# Tic_Tac_Toe.net
KiCad netlist of a schematic drawn in EAGLE
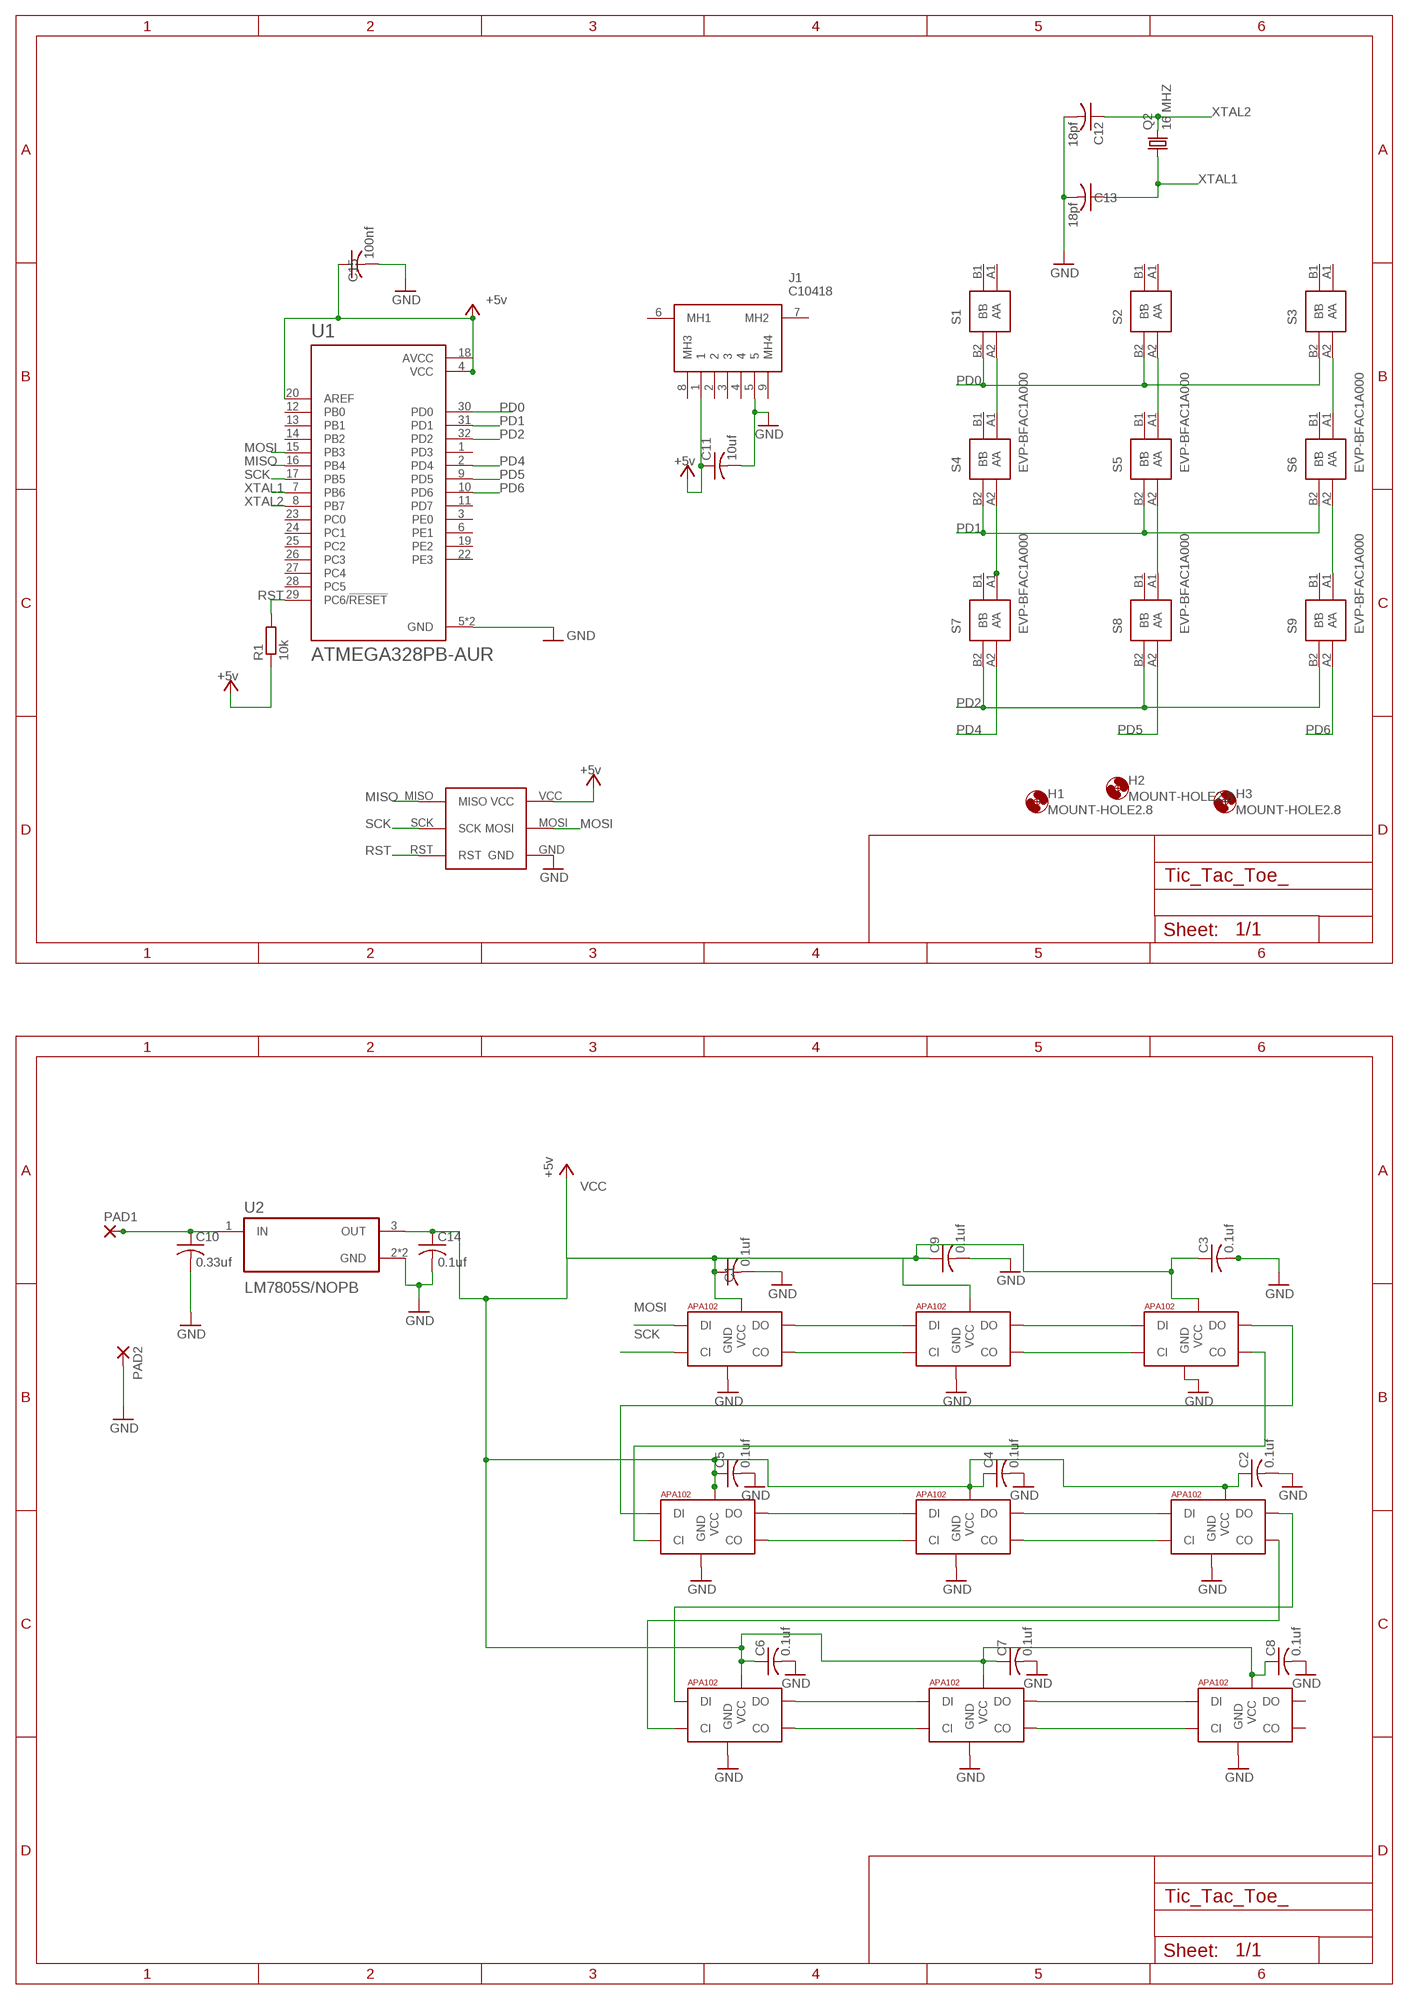
[diagram p0: schematic, sheet 1]

(export (version "E")
  (design (tool "Eeschema 10.0.6"))
  (components
    (comp (ref "C1")
      (value "0.1uf")
      (footprint "eagle-import:C0805")
      (libsource (lib "eagle-import") (part "C-USC0805"))
    )
    (comp (ref "C2")
      (value "0.1uf")
      (footprint "eagle-import:C0805")
      (libsource (lib "eagle-import") (part "C-USC0805"))
    )
    (comp (ref "C3")
      (value "0.1uf")
      (footprint "eagle-import:C0805")
      (libsource (lib "eagle-import") (part "C-USC0805"))
    )
    (comp (ref "C4")
      (value "0.1uf")
      (footprint "eagle-import:C0805")
      (libsource (lib "eagle-import") (part "C-USC0805"))
    )
    (comp (ref "C5")
      (value "0.1uf")
      (footprint "eagle-import:C0805")
      (libsource (lib "eagle-import") (part "C-USC0805"))
    )
    (comp (ref "C6")
      (value "0.1uf")
      (footprint "eagle-import:C0805")
      (libsource (lib "eagle-import") (part "C-USC0805"))
    )
    (comp (ref "C7")
      (value "0.1uf")
      (footprint "eagle-import:C0805")
      (libsource (lib "eagle-import") (part "C-USC0805"))
    )
    (comp (ref "C8")
      (value "0.1uf")
      (footprint "eagle-import:C0805")
      (libsource (lib "eagle-import") (part "C-USC0805"))
    )
    (comp (ref "C9")
      (value "0.1uf")
      (footprint "eagle-import:C0805")
      (libsource (lib "eagle-import") (part "C-USC0805"))
    )
    (comp (ref "C10")
      (value "0.33uf")
      (footprint "eagle-import:C0805")
      (libsource (lib "eagle-import") (part "C-USC0805"))
    )
    (comp (ref "C11")
      (value "10uf")
      (footprint "eagle-import:C0805")
      (libsource (lib "eagle-import") (part "C-USC0805"))
    )
    (comp (ref "C12")
      (value "18pf")
      (footprint "eagle-import:C0805")
      (libsource (lib "eagle-import") (part "C-USC0805"))
    )
    (comp (ref "C13")
      (value "18pf")
      (footprint "eagle-import:C0805")
      (libsource (lib "eagle-import") (part "C-USC0805"))
    )
    (comp (ref "C14")
      (value "0.1uf")
      (footprint "eagle-import:C0805")
      (libsource (lib "eagle-import") (part "C-USC0805"))
    )
    (comp (ref "C15")
      (value "100nf")
      (footprint "eagle-import:C0805")
      (libsource (lib "eagle-import") (part "C-USC0805"))
    )
    (comp (ref "H1")
      (value "MOUNT-HOLE2.8")
      (footprint "eagle-import:2,8")
      (libsource (lib "eagle-import") (part "MOUNT-HOLE2.8"))
    )
    (comp (ref "H2")
      (value "MOUNT-HOLE2.8")
      (footprint "eagle-import:2,8")
      (libsource (lib "eagle-import") (part "MOUNT-HOLE2.8"))
    )
    (comp (ref "H3")
      (value "MOUNT-HOLE2.8")
      (footprint "eagle-import:2,8")
      (libsource (lib "eagle-import") (part "MOUNT-HOLE2.8"))
    )
    (comp (ref "J1")
      (value "C10418")
      (footprint "eagle-import:C10418")
      (libsource (lib "eagle-import") (part "C10418"))
    )
    (comp (ref "PAD1")
      (value "2,15/1,0")
      (footprint "eagle-import:2,15_1,0")
      (libsource (lib "eagle-import") (part "2,15/1,0"))
    )
    (comp (ref "PAD2")
      (value "2,15/1,0")
      (footprint "eagle-import:2,15_1,0")
      (libsource (lib "eagle-import") (part "2,15/1,0"))
    )
    (comp (ref "Q2")
      (value "16 MHZ")
      (footprint "eagle-import:HC49UP")
      (libsource (lib "eagle-import") (part "CRYSTALHC49UP"))
    )
    (comp (ref "R1")
      (value "10k")
      (footprint "eagle-import:M0805")
      (libsource (lib "eagle-import") (part "R-EU_M0805"))
    )
    (comp (ref "S1")
      (value "EVP-BFAC1A000")
      (footprint "eagle-import:EVPBFAC1A000")
      (fields (field (name "MF") "Panasonic Electronic"))
      (libsource (lib "eagle-import") (part "EVP-BFAC1A000"))
    )
    (comp (ref "S2")
      (value "EVP-BFAC1A000")
      (footprint "eagle-import:EVPBFAC1A000")
      (fields (field (name "MF") "Panasonic Electronic"))
      (libsource (lib "eagle-import") (part "EVP-BFAC1A000"))
    )
    (comp (ref "S3")
      (value "EVP-BFAC1A000")
      (footprint "eagle-import:EVPBFAC1A000")
      (fields (field (name "MF") "Panasonic Electronic"))
      (libsource (lib "eagle-import") (part "EVP-BFAC1A000"))
    )
    (comp (ref "S4")
      (value "EVP-BFAC1A000")
      (footprint "eagle-import:EVPBFAC1A000")
      (fields (field (name "MF") "Panasonic Electronic"))
      (libsource (lib "eagle-import") (part "EVP-BFAC1A000"))
    )
    (comp (ref "S5")
      (value "EVP-BFAC1A000")
      (footprint "eagle-import:EVPBFAC1A000")
      (fields (field (name "MF") "Panasonic Electronic"))
      (libsource (lib "eagle-import") (part "EVP-BFAC1A000"))
    )
    (comp (ref "S6")
      (value "EVP-BFAC1A000")
      (footprint "eagle-import:EVPBFAC1A000")
      (fields (field (name "MF") "Panasonic Electronic"))
      (libsource (lib "eagle-import") (part "EVP-BFAC1A000"))
    )
    (comp (ref "S7")
      (value "EVP-BFAC1A000")
      (footprint "eagle-import:EVPBFAC1A000")
      (fields (field (name "MF") "Panasonic Electronic"))
      (libsource (lib "eagle-import") (part "EVP-BFAC1A000"))
    )
    (comp (ref "S8")
      (value "EVP-BFAC1A000")
      (footprint "eagle-import:EVPBFAC1A000")
      (fields (field (name "MF") "Panasonic Electronic"))
      (libsource (lib "eagle-import") (part "EVP-BFAC1A000"))
    )
    (comp (ref "S9")
      (value "EVP-BFAC1A000")
      (footprint "eagle-import:EVPBFAC1A000")
      (fields (field (name "MF") "Panasonic Electronic"))
      (libsource (lib "eagle-import") (part "EVP-BFAC1A000"))
    )
    (comp (ref "U$1")
      (value "AVR-ISP")
      (footprint "eagle-import:AVR-ISP")
      (fields (field (name "MF") "Gravitech"))
      (libsource (lib "eagle-import") (part "AVR-ISP"))
    )
    (comp (ref "U$2")
      (value "APA1025050")
      (footprint "eagle-import:APA102_5050")
      (libsource (lib "eagle-import") (part "APA1025050"))
    )
    (comp (ref "U$3")
      (value "APA1025050")
      (footprint "eagle-import:APA102_5050")
      (libsource (lib "eagle-import") (part "APA1025050"))
    )
    (comp (ref "U$4")
      (value "APA1025050")
      (footprint "eagle-import:APA102_5050")
      (libsource (lib "eagle-import") (part "APA1025050"))
    )
    (comp (ref "U$5")
      (value "APA1025050")
      (footprint "eagle-import:APA102_5050")
      (libsource (lib "eagle-import") (part "APA1025050"))
    )
    (comp (ref "U$6")
      (value "APA1025050")
      (footprint "eagle-import:APA102_5050")
      (libsource (lib "eagle-import") (part "APA1025050"))
    )
    (comp (ref "U$7")
      (value "APA1025050")
      (footprint "eagle-import:APA102_5050")
      (libsource (lib "eagle-import") (part "APA1025050"))
    )
    (comp (ref "U$8")
      (value "APA1025050")
      (footprint "eagle-import:APA102_5050")
      (libsource (lib "eagle-import") (part "APA1025050"))
    )
    (comp (ref "U$9")
      (value "APA1025050")
      (footprint "eagle-import:APA102_5050")
      (libsource (lib "eagle-import") (part "APA1025050"))
    )
    (comp (ref "U$10")
      (value "APA1025050")
      (footprint "eagle-import:APA102_5050")
      (libsource (lib "eagle-import") (part "APA1025050"))
    )
    (comp (ref "U1")
      (value "ATMEGA328PB-AUR")
      (footprint "eagle-import:QFP80P900X900X120-32N")
      (fields (field (name "DIGI-KEY_PART_NUMBER") "ATMEGA328PB-AURCT-ND") (field (name "MF") "Microchip"))
      (libsource (lib "eagle-import") (part "ATMEGA328PB-AUR"))
    )
    (comp (ref "U2")
      (value "LM7805S/NOPB")
      (footprint "eagle-import:TO254P1524X483-4N")
      (fields (field (name "MF") "Texas Instruments"))
      (libsource (lib "eagle-import") (part "LM7805S/NOPB"))
    )
  )
  (nets
    (net (code "1") (name "+5v") (class "Default")
      (node (ref "C1") (pin "1") (pinfunction "1_1") (pintype "passive"))
      (node (ref "C11") (pin "1") (pinfunction "1_1") (pintype "passive"))
      (node (ref "C14") (pin "1") (pinfunction "1_1") (pintype "passive"))
      (node (ref "C15") (pin "1") (pinfunction "1_1") (pintype "passive"))
      (node (ref "C2") (pin "1") (pinfunction "1_1") (pintype "passive"))
      (node (ref "C3") (pin "1") (pinfunction "1_1") (pintype "passive"))
      (node (ref "C4") (pin "1") (pinfunction "1_1") (pintype "passive"))
      (node (ref "C5") (pin "1") (pinfunction "1_1") (pintype "passive"))
      (node (ref "C6") (pin "1") (pinfunction "1_1") (pintype "passive"))
      (node (ref "C7") (pin "1") (pinfunction "1_1") (pintype "passive"))
      (node (ref "C8") (pin "1") (pinfunction "1_1") (pintype "passive"))
      (node (ref "C9") (pin "1") (pinfunction "1_1") (pintype "passive"))
      (node (ref "J1") (pin "1") (pinfunction "1_1") (pintype "bidirectional"))
      (node (ref "R1") (pin "1") (pinfunction "1_1") (pintype "passive"))
      (node (ref "U$1") (pin "VCC") (pinfunction "VCC_VCC") (pintype "bidirectional"))
      (node (ref "U$10") (pin "1") (pinfunction "VCC_1") (pintype "bidirectional"))
      (node (ref "U$2") (pin "1") (pinfunction "VCC_1") (pintype "bidirectional"))
      (node (ref "U$3") (pin "1") (pinfunction "VCC_1") (pintype "bidirectional"))
      (node (ref "U$4") (pin "1") (pinfunction "VCC_1") (pintype "bidirectional"))
      (node (ref "U$5") (pin "1") (pinfunction "VCC_1") (pintype "bidirectional"))
      (node (ref "U$6") (pin "1") (pinfunction "VCC_1") (pintype "bidirectional"))
      (node (ref "U$7") (pin "1") (pinfunction "VCC_1") (pintype "bidirectional"))
      (node (ref "U$8") (pin "1") (pinfunction "VCC_1") (pintype "bidirectional"))
      (node (ref "U$9") (pin "1") (pinfunction "VCC_1") (pintype "bidirectional"))
      (node (ref "U1") (pin "18") (pinfunction "AVCC_18") (pintype "power_in"))
      (node (ref "U1") (pin "20") (pinfunction "AREF_20") (pintype "input"))
      (node (ref "U1") (pin "4") (pinfunction "VCC_4") (pintype "power_in"))
      (node (ref "U2") (pin "3") (pinfunction "OUT_3") (pintype "output"))
    )
    (net (code "2") (name "/MISO") (class "Default")
      (node (ref "U$1") (pin "MISO") (pinfunction "MISO_MISO") (pintype "bidirectional"))
      (node (ref "U1") (pin "16") (pinfunction "PB4_16") (pintype "bidirectional"))
    )
    (net (code "3") (name "/MOSI") (class "Default")
      (node (ref "U$1") (pin "MOSI") (pinfunction "MOSI_MOSI") (pintype "bidirectional"))
      (node (ref "U$2") (pin "4") (pinfunction "DI_4") (pintype "bidirectional"))
      (node (ref "U1") (pin "15") (pinfunction "PB3_15") (pintype "bidirectional"))
    )
    (net (code "4") (name "/PD0") (class "Default")
      (node (ref "S1") (pin "B2") (pinfunction "B'_B2") (pintype "bidirectional"))
      (node (ref "S2") (pin "B2") (pinfunction "B'_B2") (pintype "bidirectional"))
      (node (ref "S3") (pin "B2") (pinfunction "B'_B2") (pintype "bidirectional"))
      (node (ref "U1") (pin "30") (pinfunction "PD0_30") (pintype "bidirectional"))
    )
    (net (code "5") (name "/PD1") (class "Default")
      (node (ref "S4") (pin "B2") (pinfunction "B'_B2") (pintype "bidirectional"))
      (node (ref "S5") (pin "B2") (pinfunction "B'_B2") (pintype "bidirectional"))
      (node (ref "S6") (pin "B2") (pinfunction "B'_B2") (pintype "bidirectional"))
      (node (ref "U1") (pin "31") (pinfunction "PD1_31") (pintype "bidirectional"))
    )
    (net (code "6") (name "/PD2") (class "Default")
      (node (ref "S7") (pin "B2") (pinfunction "B'_B2") (pintype "bidirectional"))
      (node (ref "S8") (pin "B2") (pinfunction "B'_B2") (pintype "bidirectional"))
      (node (ref "S9") (pin "B2") (pinfunction "B'_B2") (pintype "bidirectional"))
      (node (ref "U1") (pin "32") (pinfunction "PD2_32") (pintype "bidirectional"))
    )
    (net (code "7") (name "/PD4") (class "Default")
      (node (ref "S7") (pin "A2") (pinfunction "A'_A2") (pintype "bidirectional"))
      (node (ref "U1") (pin "2") (pinfunction "PD4_2") (pintype "bidirectional"))
    )
    (net (code "8") (name "/PD5") (class "Default")
      (node (ref "S8") (pin "A2") (pinfunction "A'_A2") (pintype "bidirectional"))
      (node (ref "U1") (pin "9") (pinfunction "PD5_9") (pintype "bidirectional"))
    )
    (net (code "9") (name "/PD6") (class "Default")
      (node (ref "S9") (pin "A2") (pinfunction "A'_A2") (pintype "bidirectional"))
      (node (ref "U1") (pin "10") (pinfunction "PD6_10") (pintype "bidirectional"))
    )
    (net (code "10") (name "/RST") (class "Default")
      (node (ref "R1") (pin "2") (pinfunction "2_2") (pintype "passive"))
      (node (ref "U$1") (pin "RST") (pinfunction "RST_RST") (pintype "bidirectional"))
      (node (ref "U1") (pin "29") (pinfunction "PC6/~{RESET}_29") (pintype "bidirectional"))
    )
    (net (code "11") (name "/SCK") (class "Default")
      (node (ref "U$1") (pin "SCK") (pinfunction "SCK_SCK") (pintype "bidirectional"))
      (node (ref "U$2") (pin "5") (pinfunction "CI_5") (pintype "bidirectional"))
      (node (ref "U1") (pin "17") (pinfunction "PB5_17") (pintype "bidirectional"))
    )
    (net (code "12") (name "/XTAL1") (class "Default")
      (node (ref "C13") (pin "1") (pinfunction "1_1") (pintype "passive"))
      (node (ref "Q2") (pin "1") (pinfunction "1_1") (pintype "passive"))
      (node (ref "U1") (pin "7") (pinfunction "PB6_7") (pintype "bidirectional"))
    )
    (net (code "13") (name "/XTAL2") (class "Default")
      (node (ref "C12") (pin "1") (pinfunction "1_1") (pintype "passive"))
      (node (ref "Q2") (pin "2") (pinfunction "2_2") (pintype "passive"))
      (node (ref "U1") (pin "8") (pinfunction "PB7_8") (pintype "bidirectional"))
    )
    (net (code "14") (name "GND") (class "Default")
      (node (ref "C1") (pin "2") (pinfunction "2_2") (pintype "passive"))
      (node (ref "C10") (pin "2") (pinfunction "2_2") (pintype "passive"))
      (node (ref "C11") (pin "2") (pinfunction "2_2") (pintype "passive"))
      (node (ref "C12") (pin "2") (pinfunction "2_2") (pintype "passive"))
      (node (ref "C13") (pin "2") (pinfunction "2_2") (pintype "passive"))
      (node (ref "C14") (pin "2") (pinfunction "2_2") (pintype "passive"))
      (node (ref "C15") (pin "2") (pinfunction "2_2") (pintype "passive"))
      (node (ref "C2") (pin "2") (pinfunction "2_2") (pintype "passive"))
      (node (ref "C3") (pin "2") (pinfunction "2_2") (pintype "passive"))
      (node (ref "C4") (pin "2") (pinfunction "2_2") (pintype "passive"))
      (node (ref "C5") (pin "2") (pinfunction "2_2") (pintype "passive"))
      (node (ref "C6") (pin "2") (pinfunction "2_2") (pintype "passive"))
      (node (ref "C7") (pin "2") (pinfunction "2_2") (pintype "passive"))
      (node (ref "C8") (pin "2") (pinfunction "2_2") (pintype "passive"))
      (node (ref "C9") (pin "2") (pinfunction "2_2") (pintype "passive"))
      (node (ref "J1") (pin "5") (pinfunction "5_5") (pintype "bidirectional"))
      (node (ref "PAD2") (pin "1") (pinfunction "P_1") (pintype "passive"))
      (node (ref "U$1") (pin "GND") (pinfunction "GND_GND") (pintype "bidirectional"))
      (node (ref "U$10") (pin "6") (pinfunction "GND_6") (pintype "bidirectional"))
      (node (ref "U$2") (pin "6") (pinfunction "GND_6") (pintype "bidirectional"))
      (node (ref "U$3") (pin "6") (pinfunction "GND_6") (pintype "bidirectional"))
      (node (ref "U$4") (pin "6") (pinfunction "GND_6") (pintype "bidirectional"))
      (node (ref "U$5") (pin "6") (pinfunction "GND_6") (pintype "bidirectional"))
      (node (ref "U$6") (pin "6") (pinfunction "GND_6") (pintype "bidirectional"))
      (node (ref "U$7") (pin "6") (pinfunction "GND_6") (pintype "bidirectional"))
      (node (ref "U$8") (pin "6") (pinfunction "GND_6") (pintype "bidirectional"))
      (node (ref "U$9") (pin "6") (pinfunction "GND_6") (pintype "bidirectional"))
      (node (ref "U1") (pin "21") (pinfunction "GND_21") (pintype "power_in"))
      (node (ref "U1") (pin "5") (pinfunction "GND_5") (pintype "power_in"))
      (node (ref "U2") (pin "2") (pinfunction "GND_2") (pintype "power_in"))
      (node (ref "U2") (pin "4") (pinfunction "GND_4") (pintype "power_in"))
    )
    (net (code "15") (name "Net-(PAD1-P)") (class "Default")
      (node (ref "C10") (pin "1") (pinfunction "1_1") (pintype "passive"))
      (node (ref "PAD1") (pin "1") (pinfunction "P_1") (pintype "passive"))
      (node (ref "U2") (pin "1") (pinfunction "IN_1") (pintype "input"))
    )
    (net (code "16") (name "Net-(S1-A')") (class "Default")
      (node (ref "S1") (pin "A2") (pinfunction "A'_A2") (pintype "bidirectional"))
      (node (ref "S4") (pin "A1") (pinfunction "A_A1") (pintype "bidirectional"))
    )
    (net (code "17") (name "Net-(S2-A')") (class "Default")
      (node (ref "S2") (pin "A2") (pinfunction "A'_A2") (pintype "bidirectional"))
      (node (ref "S5") (pin "A1") (pinfunction "A_A1") (pintype "bidirectional"))
    )
    (net (code "18") (name "Net-(S3-A')") (class "Default")
      (node (ref "S3") (pin "A2") (pinfunction "A'_A2") (pintype "bidirectional"))
      (node (ref "S6") (pin "A1") (pinfunction "A_A1") (pintype "bidirectional"))
    )
    (net (code "19") (name "Net-(S4-A')") (class "Default")
      (node (ref "S4") (pin "A2") (pinfunction "A'_A2") (pintype "bidirectional"))
      (node (ref "S7") (pin "A1") (pinfunction "A_A1") (pintype "bidirectional"))
    )
    (net (code "20") (name "Net-(S5-A')") (class "Default")
      (node (ref "S5") (pin "A2") (pinfunction "A'_A2") (pintype "bidirectional"))
      (node (ref "S8") (pin "A1") (pinfunction "A_A1") (pintype "bidirectional"))
    )
    (net (code "21") (name "Net-(S6-A')") (class "Default")
      (node (ref "S6") (pin "A2") (pinfunction "A'_A2") (pintype "bidirectional"))
      (node (ref "S9") (pin "A1") (pinfunction "A_A1") (pintype "bidirectional"))
    )
    (net (code "22") (name "Net-(U$2-CO)") (class "Default")
      (node (ref "U$2") (pin "2") (pinfunction "CO_2") (pintype "bidirectional"))
      (node (ref "U$3") (pin "5") (pinfunction "CI_5") (pintype "bidirectional"))
    )
    (net (code "23") (name "Net-(U$2-DO)") (class "Default")
      (node (ref "U$2") (pin "3") (pinfunction "DO_3") (pintype "bidirectional"))
      (node (ref "U$3") (pin "4") (pinfunction "DI_4") (pintype "bidirectional"))
    )
    (net (code "24") (name "Net-(U$3-CO)") (class "Default")
      (node (ref "U$3") (pin "2") (pinfunction "CO_2") (pintype "bidirectional"))
      (node (ref "U$4") (pin "5") (pinfunction "CI_5") (pintype "bidirectional"))
    )
    (net (code "25") (name "Net-(U$3-DO)") (class "Default")
      (node (ref "U$3") (pin "3") (pinfunction "DO_3") (pintype "bidirectional"))
      (node (ref "U$4") (pin "4") (pinfunction "DI_4") (pintype "bidirectional"))
    )
    (net (code "26") (name "Net-(U$4-CO)") (class "Default")
      (node (ref "U$4") (pin "2") (pinfunction "CO_2") (pintype "bidirectional"))
      (node (ref "U$5") (pin "5") (pinfunction "CI_5") (pintype "bidirectional"))
    )
    (net (code "27") (name "Net-(U$4-DO)") (class "Default")
      (node (ref "U$4") (pin "3") (pinfunction "DO_3") (pintype "bidirectional"))
      (node (ref "U$5") (pin "4") (pinfunction "DI_4") (pintype "bidirectional"))
    )
    (net (code "28") (name "Net-(U$5-CO)") (class "Default")
      (node (ref "U$5") (pin "2") (pinfunction "CO_2") (pintype "bidirectional"))
      (node (ref "U$6") (pin "5") (pinfunction "CI_5") (pintype "bidirectional"))
    )
    (net (code "29") (name "Net-(U$5-DO)") (class "Default")
      (node (ref "U$5") (pin "3") (pinfunction "DO_3") (pintype "bidirectional"))
      (node (ref "U$6") (pin "4") (pinfunction "DI_4") (pintype "bidirectional"))
    )
    (net (code "30") (name "Net-(U$6-CO)") (class "Default")
      (node (ref "U$6") (pin "2") (pinfunction "CO_2") (pintype "bidirectional"))
      (node (ref "U$7") (pin "5") (pinfunction "CI_5") (pintype "bidirectional"))
    )
    (net (code "31") (name "Net-(U$6-DO)") (class "Default")
      (node (ref "U$6") (pin "3") (pinfunction "DO_3") (pintype "bidirectional"))
      (node (ref "U$7") (pin "4") (pinfunction "DI_4") (pintype "bidirectional"))
    )
    (net (code "32") (name "Net-(U$7-CO)") (class "Default")
      (node (ref "U$7") (pin "2") (pinfunction "CO_2") (pintype "bidirectional"))
      (node (ref "U$8") (pin "5") (pinfunction "CI_5") (pintype "bidirectional"))
    )
    (net (code "33") (name "Net-(U$7-DO)") (class "Default")
      (node (ref "U$7") (pin "3") (pinfunction "DO_3") (pintype "bidirectional"))
      (node (ref "U$8") (pin "4") (pinfunction "DI_4") (pintype "bidirectional"))
    )
    (net (code "34") (name "Net-(U$8-CO)") (class "Default")
      (node (ref "U$8") (pin "2") (pinfunction "CO_2") (pintype "bidirectional"))
      (node (ref "U$9") (pin "5") (pinfunction "CI_5") (pintype "bidirectional"))
    )
    (net (code "35") (name "Net-(U$8-DO)") (class "Default")
      (node (ref "U$8") (pin "3") (pinfunction "DO_3") (pintype "bidirectional"))
      (node (ref "U$9") (pin "4") (pinfunction "DI_4") (pintype "bidirectional"))
    )
    (net (code "36") (name "Net-(U$10-CI)") (class "Default")
      (node (ref "U$10") (pin "5") (pinfunction "CI_5") (pintype "bidirectional"))
      (node (ref "U$9") (pin "2") (pinfunction "CO_2") (pintype "bidirectional"))
    )
    (net (code "37") (name "Net-(U$10-DI)") (class "Default")
      (node (ref "U$10") (pin "4") (pinfunction "DI_4") (pintype "bidirectional"))
      (node (ref "U$9") (pin "3") (pinfunction "DO_3") (pintype "bidirectional"))
    )
    (net (code "38") (name "unconnected-(J1-MH1-Pad6)") (class "Default")
      (node (ref "J1") (pin "6") (pinfunction "MH1_6") (pintype "bidirectional"))
    )
    (net (code "39") (name "unconnected-(J1-MH2-Pad7)") (class "Default")
      (node (ref "J1") (pin "7") (pinfunction "MH2_7") (pintype "bidirectional"))
    )
    (net (code "40") (name "unconnected-(J1-MH3-Pad8)") (class "Default")
      (node (ref "J1") (pin "8") (pinfunction "MH3_8") (pintype "bidirectional"))
    )
    (net (code "41") (name "unconnected-(J1-MH4-Pad9)") (class "Default")
      (node (ref "J1") (pin "9") (pinfunction "MH4_9") (pintype "bidirectional"))
    )
    (net (code "42") (name "unconnected-(J1-Pad2)") (class "Default")
      (node (ref "J1") (pin "2") (pinfunction "2_2") (pintype "bidirectional"))
    )
    (net (code "43") (name "unconnected-(J1-Pad3)") (class "Default")
      (node (ref "J1") (pin "3") (pinfunction "3_3") (pintype "bidirectional"))
    )
    (net (code "44") (name "unconnected-(J1-Pad4)") (class "Default")
      (node (ref "J1") (pin "4") (pinfunction "4_4") (pintype "bidirectional"))
    )
    (net (code "45") (name "unconnected-(S1-A-PadA1)") (class "Default")
      (node (ref "S1") (pin "A1") (pinfunction "A_A1") (pintype "bidirectional"))
    )
    (net (code "46") (name "unconnected-(S1-B-PadB1)") (class "Default")
      (node (ref "S1") (pin "B1") (pinfunction "B_B1") (pintype "bidirectional"))
    )
    (net (code "47") (name "unconnected-(S2-A-PadA1)") (class "Default")
      (node (ref "S2") (pin "A1") (pinfunction "A_A1") (pintype "bidirectional"))
    )
    (net (code "48") (name "unconnected-(S2-B-PadB1)") (class "Default")
      (node (ref "S2") (pin "B1") (pinfunction "B_B1") (pintype "bidirectional"))
    )
    (net (code "49") (name "unconnected-(S3-A-PadA1)") (class "Default")
      (node (ref "S3") (pin "A1") (pinfunction "A_A1") (pintype "bidirectional"))
    )
    (net (code "50") (name "unconnected-(S3-B-PadB1)") (class "Default")
      (node (ref "S3") (pin "B1") (pinfunction "B_B1") (pintype "bidirectional"))
    )
    (net (code "51") (name "unconnected-(S4-B-PadB1)") (class "Default")
      (node (ref "S4") (pin "B1") (pinfunction "B_B1") (pintype "bidirectional"))
    )
    (net (code "52") (name "unconnected-(S5-B-PadB1)") (class "Default")
      (node (ref "S5") (pin "B1") (pinfunction "B_B1") (pintype "bidirectional"))
    )
    (net (code "53") (name "unconnected-(S6-B-PadB1)") (class "Default")
      (node (ref "S6") (pin "B1") (pinfunction "B_B1") (pintype "bidirectional"))
    )
    (net (code "54") (name "unconnected-(S7-B-PadB1)") (class "Default")
      (node (ref "S7") (pin "B1") (pinfunction "B_B1") (pintype "bidirectional"))
    )
    (net (code "55") (name "unconnected-(S8-B-PadB1)") (class "Default")
      (node (ref "S8") (pin "B1") (pinfunction "B_B1") (pintype "bidirectional"))
    )
    (net (code "56") (name "unconnected-(S9-B-PadB1)") (class "Default")
      (node (ref "S9") (pin "B1") (pinfunction "B_B1") (pintype "bidirectional"))
    )
    (net (code "57") (name "unconnected-(U$10-CO-Pad2)") (class "Default")
      (node (ref "U$10") (pin "2") (pinfunction "CO_2") (pintype "bidirectional"))
    )
    (net (code "58") (name "unconnected-(U$10-DO-Pad3)") (class "Default")
      (node (ref "U$10") (pin "3") (pinfunction "DO_3") (pintype "bidirectional"))
    )
    (net (code "59") (name "unconnected-(U1-PB0-Pad12)") (class "Default")
      (node (ref "U1") (pin "12") (pinfunction "PB0_12") (pintype "bidirectional"))
    )
    (net (code "60") (name "unconnected-(U1-PB1-Pad13)") (class "Default")
      (node (ref "U1") (pin "13") (pinfunction "PB1_13") (pintype "bidirectional"))
    )
    (net (code "61") (name "unconnected-(U1-PB2-Pad14)") (class "Default")
      (node (ref "U1") (pin "14") (pinfunction "PB2_14") (pintype "bidirectional"))
    )
    (net (code "62") (name "unconnected-(U1-PC0-Pad23)") (class "Default")
      (node (ref "U1") (pin "23") (pinfunction "PC0_23") (pintype "bidirectional"))
    )
    (net (code "63") (name "unconnected-(U1-PC1-Pad24)") (class "Default")
      (node (ref "U1") (pin "24") (pinfunction "PC1_24") (pintype "bidirectional"))
    )
    (net (code "64") (name "unconnected-(U1-PC2-Pad25)") (class "Default")
      (node (ref "U1") (pin "25") (pinfunction "PC2_25") (pintype "bidirectional"))
    )
    (net (code "65") (name "unconnected-(U1-PC3-Pad26)") (class "Default")
      (node (ref "U1") (pin "26") (pinfunction "PC3_26") (pintype "bidirectional"))
    )
    (net (code "66") (name "unconnected-(U1-PC4-Pad27)") (class "Default")
      (node (ref "U1") (pin "27") (pinfunction "PC4_27") (pintype "bidirectional"))
    )
    (net (code "67") (name "unconnected-(U1-PC5-Pad28)") (class "Default")
      (node (ref "U1") (pin "28") (pinfunction "PC5_28") (pintype "bidirectional"))
    )
    (net (code "68") (name "unconnected-(U1-PD3-Pad1)") (class "Default")
      (node (ref "U1") (pin "1") (pinfunction "PD3_1") (pintype "bidirectional"))
    )
    (net (code "69") (name "unconnected-(U1-PD7-Pad11)") (class "Default")
      (node (ref "U1") (pin "11") (pinfunction "PD7_11") (pintype "bidirectional"))
    )
    (net (code "70") (name "unconnected-(U1-PE0-Pad3)") (class "Default")
      (node (ref "U1") (pin "3") (pinfunction "PE0_3") (pintype "bidirectional"))
    )
    (net (code "71") (name "unconnected-(U1-PE1-Pad6)") (class "Default")
      (node (ref "U1") (pin "6") (pinfunction "PE1_6") (pintype "bidirectional"))
    )
    (net (code "72") (name "unconnected-(U1-PE2-Pad19)") (class "Default")
      (node (ref "U1") (pin "19") (pinfunction "PE2_19") (pintype "bidirectional"))
    )
    (net (code "73") (name "unconnected-(U1-PE3-Pad22)") (class "Default")
      (node (ref "U1") (pin "22") (pinfunction "PE3_22") (pintype "bidirectional"))
    )
  )
)
